# currentU_cond.net
KiCad netlist of a schematic drawn in Altium Designer
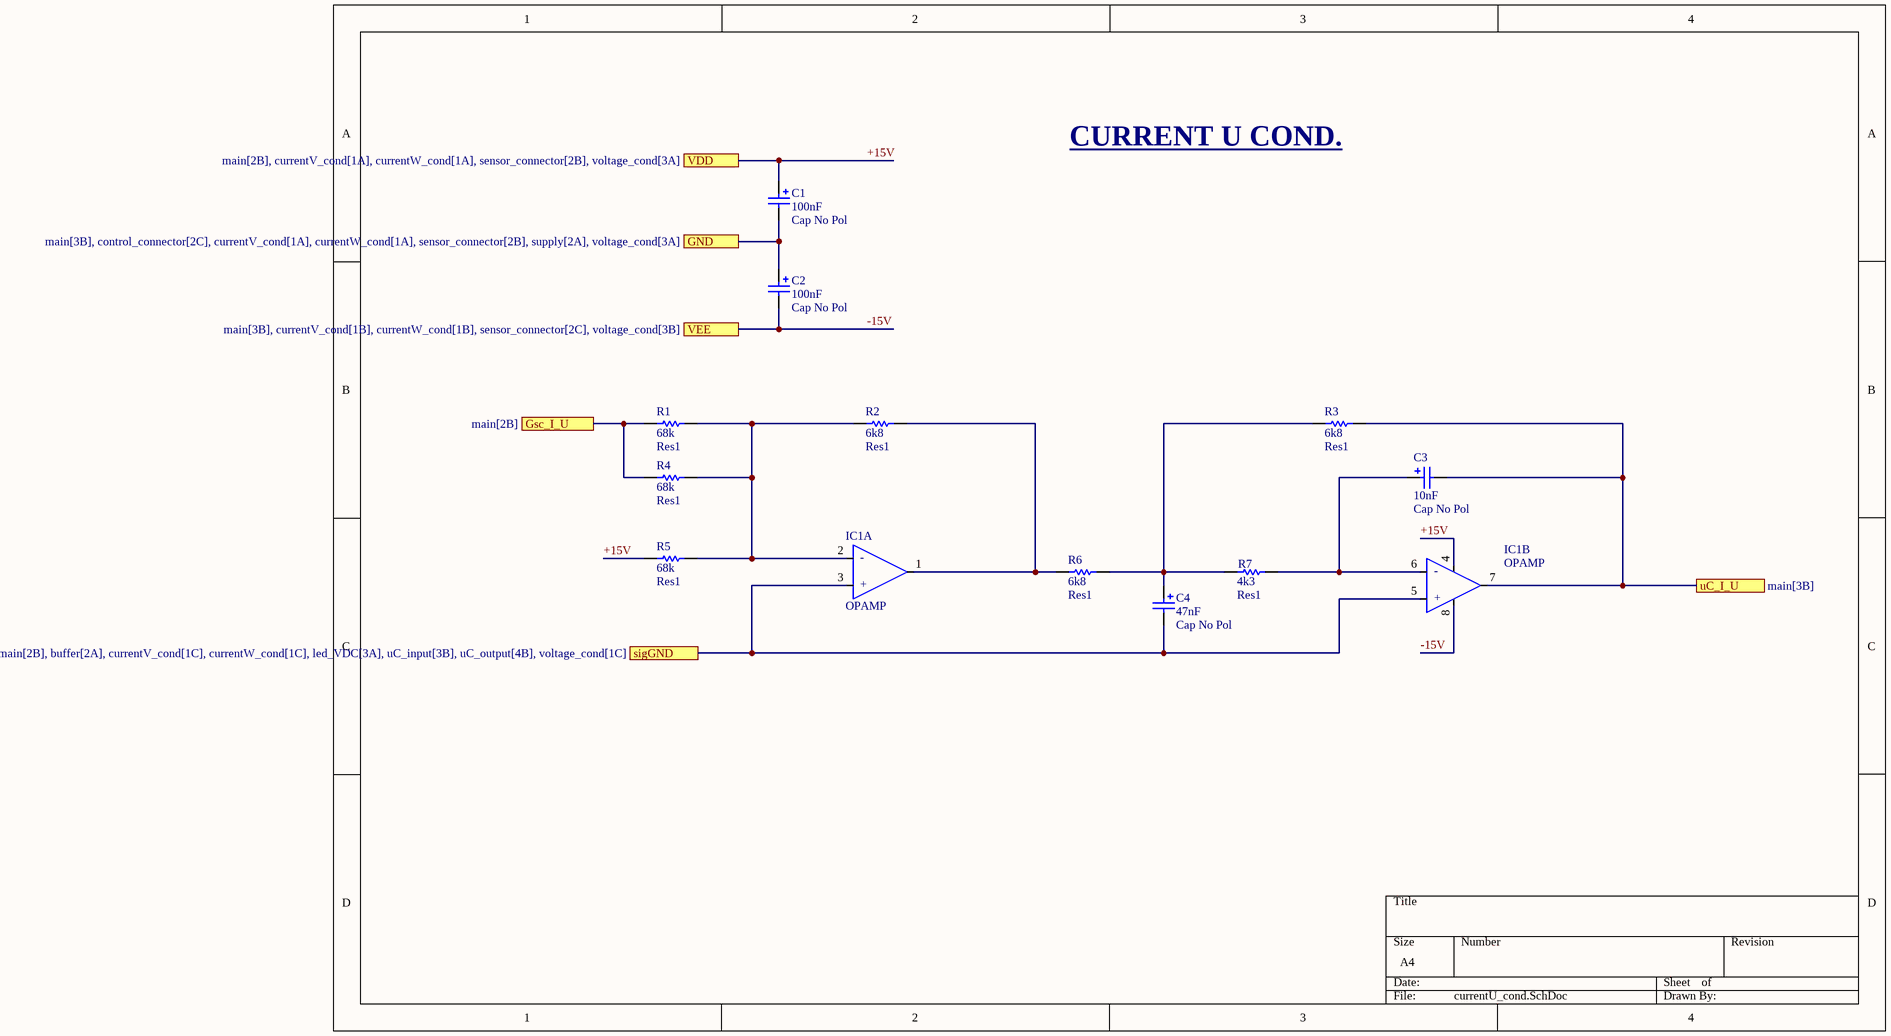
[diagram p0: currentU_cond.SchDoc]

(export (version "E")
  (design (tool "Eeschema 10.0.6"))
  (components
    (comp (ref "C1")
      (value "Cap No Pol")
      (footprint "RAD-0.1_mod")
      (description "Polarized Capacitor (Radial)")
      (fields (field (name "ALTIUM_VALUE") "100nF") (field (name "PUBLISHER") "Altium Limited"))
      (libsource (lib "LABSTEPS_Project") (part "Cap No Pol"))
    )
    (comp (ref "C2")
      (value "Cap No Pol")
      (footprint "RAD-0.1_mod")
      (description "Polarized Capacitor (Radial)")
      (fields (field (name "ALTIUM_VALUE") "100nF") (field (name "PUBLISHER") "Altium Limited"))
      (libsource (lib "LABSTEPS_Project") (part "Cap No Pol"))
    )
    (comp (ref "C3")
      (value "Cap No Pol")
      (footprint "RAD-0.1_mod")
      (description "Polarized Capacitor (Radial)")
      (fields (field (name "ALTIUM_VALUE") "10nF") (field (name "PUBLISHER") "Altium Limited"))
      (libsource (lib "LABSTEPS_Project") (part "Cap No Pol"))
    )
    (comp (ref "C4")
      (value "Cap No Pol")
      (footprint "RAD-0.1_mod")
      (description "Polarized Capacitor (Radial)")
      (fields (field (name "ALTIUM_VALUE") "47nF") (field (name "PUBLISHER") "Altium Limited"))
      (libsource (lib "LABSTEPS_Project") (part "Cap No Pol"))
    )
    (comp (ref "IC1")
      (value "OPAMP")
      (footprint "DIP-8_mod")
      (description "ADTL082")
      (libsource (lib "LABSTEPS_Project") (part "ADTL082"))
    )
    (comp (ref "R1")
      (value "Res1")
      (footprint "AXIAL-0.3_mod")
      (description "Resistor")
      (fields (field (name "ALTIUM_VALUE") "68k") (field (name "PUBLISHER") "Altium Limited"))
      (libsource (lib "LABSTEPS_Project") (part "Res1"))
    )
    (comp (ref "R2")
      (value "Res1")
      (footprint "AXIAL-0.3_mod")
      (description "Resistor")
      (fields (field (name "ALTIUM_VALUE") "6k8") (field (name "PUBLISHER") "Altium Limited"))
      (libsource (lib "LABSTEPS_Project") (part "Res1"))
    )
    (comp (ref "R3")
      (value "Res1")
      (footprint "AXIAL-0.3_mod")
      (description "Resistor")
      (fields (field (name "ALTIUM_VALUE") "6k8") (field (name "PUBLISHER") "Altium Limited"))
      (libsource (lib "LABSTEPS_Project") (part "Res1"))
    )
    (comp (ref "R4")
      (value "Res1")
      (footprint "AXIAL-0.3_mod")
      (description "Resistor")
      (fields (field (name "ALTIUM_VALUE") "68k") (field (name "PUBLISHER") "Altium Limited"))
      (libsource (lib "LABSTEPS_Project") (part "Res1"))
    )
    (comp (ref "R5")
      (value "Res1")
      (footprint "AXIAL-0.3_mod")
      (description "Resistor")
      (fields (field (name "ALTIUM_VALUE") "68k") (field (name "PUBLISHER") "Altium Limited"))
      (libsource (lib "LABSTEPS_Project") (part "Res1"))
    )
    (comp (ref "R6")
      (value "Res1")
      (footprint "AXIAL-0.3_mod")
      (description "Resistor")
      (fields (field (name "ALTIUM_VALUE") "6k8") (field (name "PUBLISHER") "Altium Limited"))
      (libsource (lib "LABSTEPS_Project") (part "Res1"))
    )
    (comp (ref "R7")
      (value "Res1")
      (footprint "AXIAL-0.3_mod")
      (description "Resistor")
      (fields (field (name "ALTIUM_VALUE") "4k3") (field (name "PUBLISHER") "Altium Limited"))
      (libsource (lib "LABSTEPS_Project") (part "Res1"))
    )
  )
  (nets
    (net (code "1") (name "/+15V") (class "Default")
      (node (ref "C1") (pin "1") (pinfunction "1_1") (pintype "passive"))
      (node (ref "IC1") (pin "4") (pinfunction "-V_4") (pintype "passive"))
      (node (ref "R5") (pin "1") (pinfunction "1_1") (pintype "passive"))
    )
    (net (code "2") (name "/-15V") (class "Default")
      (node (ref "C2") (pin "2") (pinfunction "2_2") (pintype "passive"))
      (node (ref "IC1") (pin "8") (pinfunction "V+_8") (pintype "passive"))
    )
    (net (code "3") (name "/GND") (class "Default")
      (node (ref "C1") (pin "2") (pinfunction "2_2") (pintype "passive"))
      (node (ref "C2") (pin "1") (pinfunction "1_1") (pintype "passive"))
    )
    (net (code "4") (name "/Gsc_I_U") (class "Default")
      (node (ref "R1") (pin "1") (pinfunction "1_1") (pintype "passive"))
      (node (ref "R4") (pin "1") (pinfunction "1_1") (pintype "passive"))
    )
    (net (code "5") (name "/sigGND") (class "Default")
      (node (ref "C4") (pin "2") (pinfunction "2_2") (pintype "passive"))
      (node (ref "IC1") (pin "3") (pinfunction "IN_A_+_3") (pintype "passive"))
      (node (ref "IC1") (pin "5") (pinfunction "IN_B_+_5") (pintype "passive"))
    )
    (net (code "6") (name "/uC_I_U") (class "Default")
      (node (ref "C3") (pin "2") (pinfunction "2_2") (pintype "passive"))
      (node (ref "IC1") (pin "7") (pinfunction "OUT_B_7") (pintype "passive"))
      (node (ref "R3") (pin "2") (pinfunction "2_2") (pintype "passive"))
    )
    (net (code "7") (name "Net-(C4-Pad1)") (class "Default")
      (node (ref "C4") (pin "1") (pinfunction "1_1") (pintype "passive"))
      (node (ref "R3") (pin "1") (pinfunction "1_1") (pintype "passive"))
      (node (ref "R6") (pin "2") (pinfunction "2_2") (pintype "passive"))
      (node (ref "R7") (pin "1") (pinfunction "1_1") (pintype "passive"))
    )
    (net (code "8") (name "Net-(IC1A-IN_A_-)") (class "Default")
      (node (ref "IC1") (pin "2") (pinfunction "IN_A_-_2") (pintype "passive"))
      (node (ref "R1") (pin "2") (pinfunction "2_2") (pintype "passive"))
      (node (ref "R2") (pin "1") (pinfunction "1_1") (pintype "passive"))
      (node (ref "R4") (pin "2") (pinfunction "2_2") (pintype "passive"))
      (node (ref "R5") (pin "2") (pinfunction "2_2") (pintype "passive"))
    )
    (net (code "9") (name "Net-(IC1A-OUT_A)") (class "Default")
      (node (ref "IC1") (pin "1") (pinfunction "OUT_A_1") (pintype "passive"))
      (node (ref "R2") (pin "2") (pinfunction "2_2") (pintype "passive"))
      (node (ref "R6") (pin "1") (pinfunction "1_1") (pintype "passive"))
    )
    (net (code "10") (name "Net-(IC1B-IN_B_-)") (class "Default")
      (node (ref "C3") (pin "1") (pinfunction "1_1") (pintype "passive"))
      (node (ref "IC1") (pin "6") (pinfunction "IN_B_-_6") (pintype "passive"))
      (node (ref "R7") (pin "2") (pinfunction "2_2") (pintype "passive"))
    )
  )
)
